# LITAF_TEMPTRESS.net
KiCad netlist of a schematic drawn in EAGLE
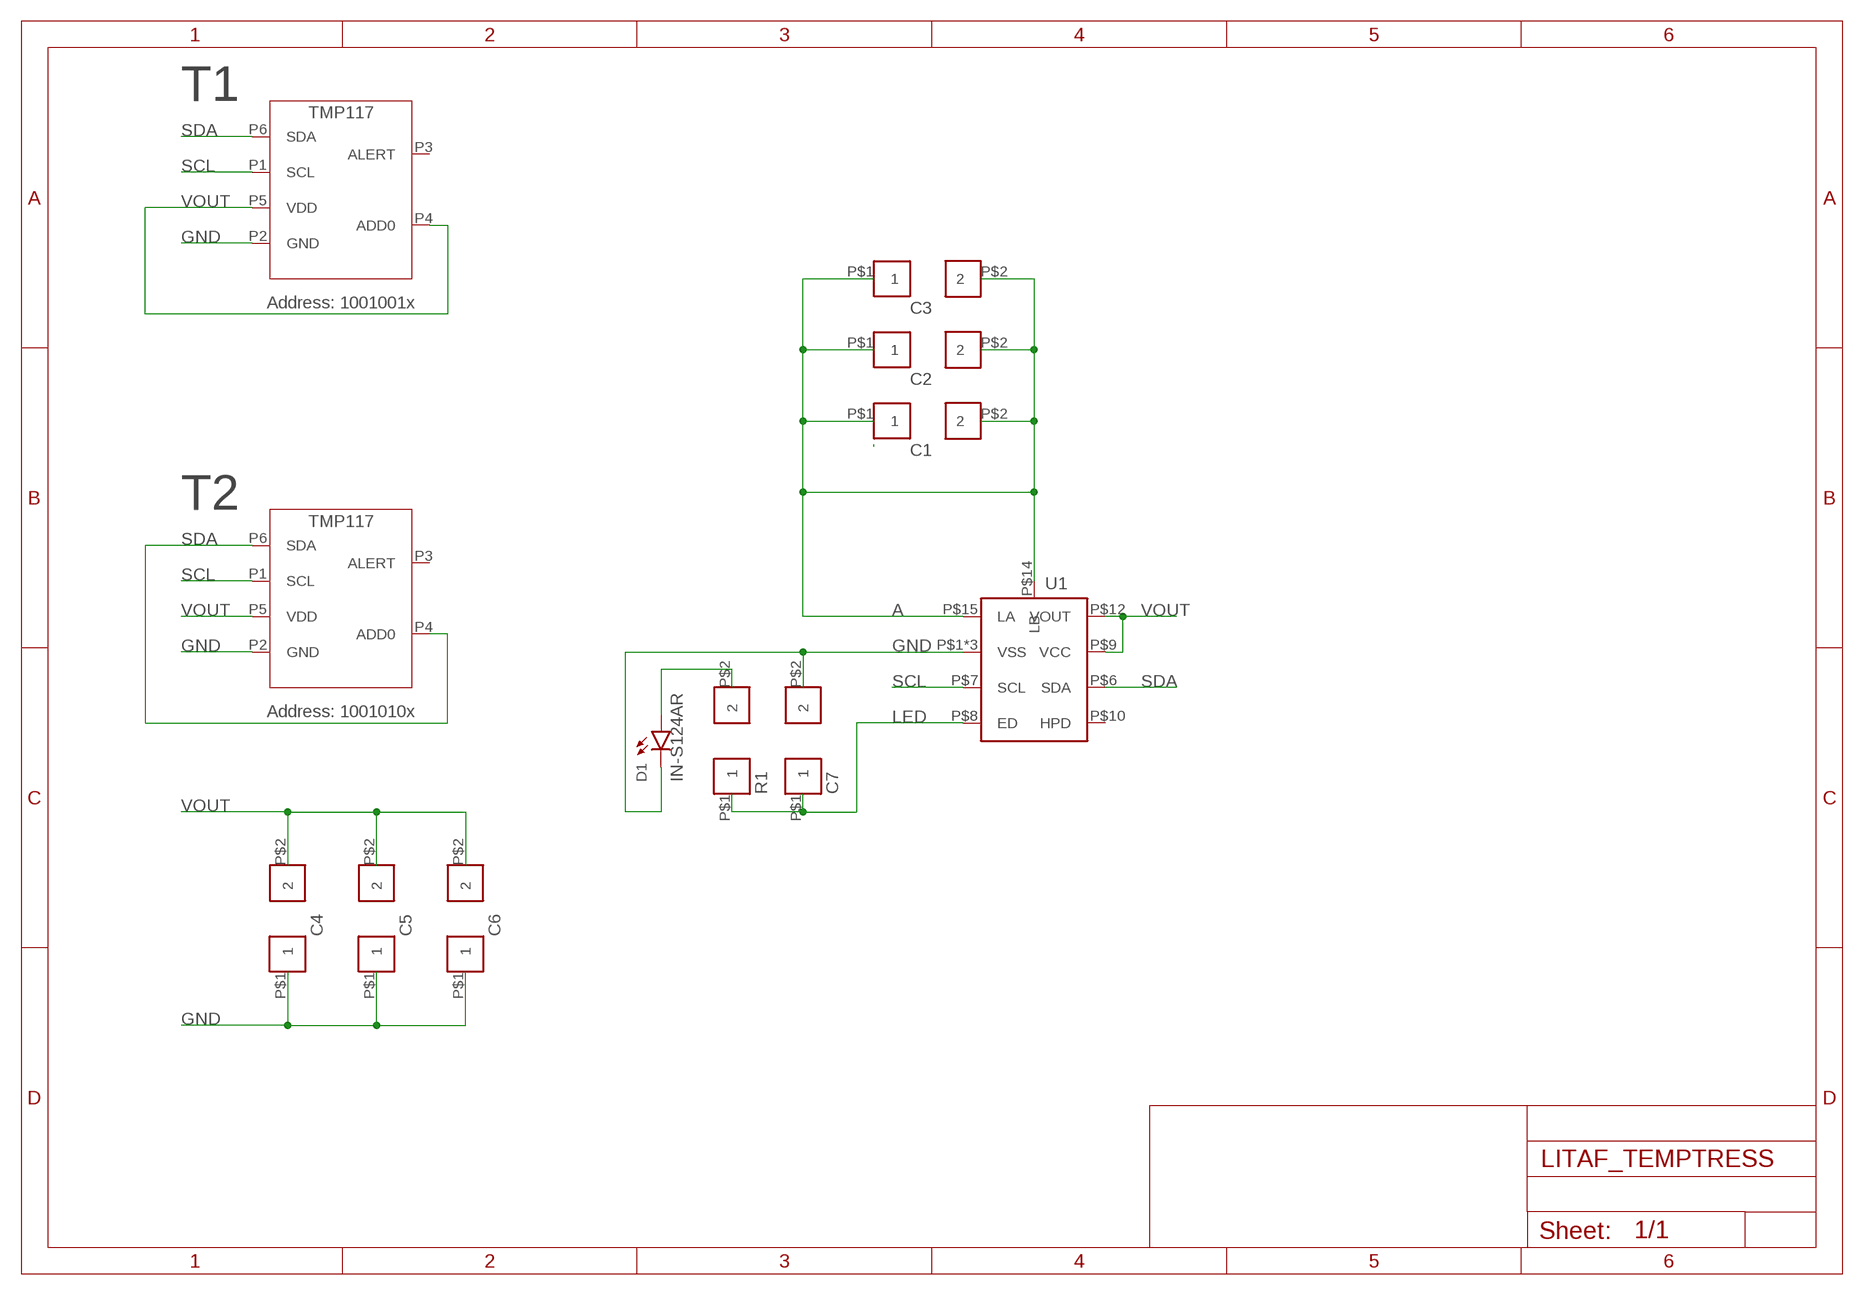
[diagram p0: schematic, sheet 1]

(export (version "E")
  (design (tool "Eeschema 10.0.6"))
  (components
    (comp (ref "C1")
      (value "0402-CAP")
      (footprint "eagle-import:0402-SMT")
      (libsource (lib "eagle-import") (part "0402-CAP"))
    )
    (comp (ref "C2")
      (value "0402-CAP")
      (footprint "eagle-import:0402-SMT")
      (libsource (lib "eagle-import") (part "0402-CAP"))
    )
    (comp (ref "C3")
      (value "0402-CAP")
      (footprint "eagle-import:0402-SMT")
      (libsource (lib "eagle-import") (part "0402-CAP"))
    )
    (comp (ref "C4")
      (value "0603-CAP")
      (footprint "eagle-import:0603-SMT[WIDE]")
      (libsource (lib "eagle-import") (part "0603-CAP"))
    )
    (comp (ref "C5")
      (value "0402-CAP")
      (footprint "eagle-import:0402-SMT")
      (libsource (lib "eagle-import") (part "0402-CAP"))
    )
    (comp (ref "C6")
      (value "0402-CAP")
      (footprint "eagle-import:0402-SMT")
      (libsource (lib "eagle-import") (part "0402-CAP"))
    )
    (comp (ref "C7")
      (value "0402-CAP")
      (footprint "eagle-import:0402-SMT")
      (libsource (lib "eagle-import") (part "0402-CAP?"))
    )
    (comp (ref "D1")
      (value "IN-S124AR")
      (footprint "eagle-import:IN-S124AR")
      (libsource (lib "eagle-import") (part "IN-S124AR"))
    )
    (comp (ref "R1")
      (value "0402-CAP")
      (footprint "eagle-import:0402-SMT")
      (libsource (lib "eagle-import") (part "0402-CAP?"))
    )
    (comp (ref "T1")
      (value "TMP117")
      (footprint "eagle-import:DRV0006B")
      (libsource (lib "eagle-import") (part "TMP117"))
    )
    (comp (ref "T2")
      (value "TMP117")
      (footprint "eagle-import:DRV0006B")
      (libsource (lib "eagle-import") (part "TMP117"))
    )
    (comp (ref "U1")
      (value "NTAG5_LINK_NTP53X2")
      (footprint "eagle-import:SOT1161-2")
      (libsource (lib "eagle-import") (part "NTAG5_LINK_NTP53X2"))
    )
  )
  (nets
    (net (code "1") (name "/A") (class "Default")
      (node (ref "C1") (pin "P$1") (pinfunction "1_P$1") (pintype "bidirectional"))
      (node (ref "C1") (pin "P$2") (pinfunction "2_P$2") (pintype "bidirectional"))
      (node (ref "C2") (pin "P$1") (pinfunction "1_P$1") (pintype "bidirectional"))
      (node (ref "C2") (pin "P$2") (pinfunction "2_P$2") (pintype "bidirectional"))
      (node (ref "C3") (pin "P$1") (pinfunction "1_P$1") (pintype "bidirectional"))
      (node (ref "C3") (pin "P$2") (pinfunction "2_P$2") (pintype "bidirectional"))
      (node (ref "U1") (pin "P$14") (pinfunction "LB_P$14") (pintype "bidirectional"))
      (node (ref "U1") (pin "P$15") (pinfunction "LA_P$15") (pintype "bidirectional"))
    )
    (net (code "2") (name "/GND") (class "Default")
      (node (ref "C4") (pin "P$1") (pinfunction "1_P$1") (pintype "bidirectional"))
      (node (ref "C5") (pin "P$1") (pinfunction "1_P$1") (pintype "bidirectional"))
      (node (ref "C6") (pin "P$1") (pinfunction "1_P$1") (pintype "bidirectional"))
      (node (ref "C7") (pin "P$2") (pinfunction "2_P$2") (pintype "bidirectional"))
      (node (ref "D1") (pin "P$2") (pinfunction "C_P$2") (pintype "passive"))
      (node (ref "T1") (pin "P2") (pinfunction "GND_P2") (pintype "bidirectional"))
      (node (ref "T2") (pin "P2") (pinfunction "GND_P2") (pintype "bidirectional"))
      (node (ref "U1") (pin "P$1") (pinfunction "VSS_P$1") (pintype "bidirectional"))
      (node (ref "U1") (pin "P$11") (pinfunction "VSS_P$11") (pintype "bidirectional"))
      (node (ref "U1") (pin "P$2") (pinfunction "VSS_P$2") (pintype "bidirectional"))
    )
    (net (code "3") (name "/LED") (class "Default")
      (node (ref "C7") (pin "P$1") (pinfunction "1_P$1") (pintype "bidirectional"))
      (node (ref "R1") (pin "P$1") (pinfunction "1_P$1") (pintype "bidirectional"))
      (node (ref "U1") (pin "P$8") (pinfunction "ED_P$8") (pintype "bidirectional"))
    )
    (net (code "4") (name "/SCL") (class "Default")
      (node (ref "T1") (pin "P1") (pinfunction "SCL_P1") (pintype "bidirectional"))
      (node (ref "T2") (pin "P1") (pinfunction "SCL_P1") (pintype "bidirectional"))
      (node (ref "U1") (pin "P$7") (pinfunction "SCL_P$7") (pintype "bidirectional"))
    )
    (net (code "5") (name "/SDA") (class "Default")
      (node (ref "T1") (pin "P6") (pinfunction "SDA_P6") (pintype "bidirectional"))
      (node (ref "T2") (pin "P4") (pinfunction "ADD0_P4") (pintype "bidirectional"))
      (node (ref "T2") (pin "P6") (pinfunction "SDA_P6") (pintype "bidirectional"))
      (node (ref "U1") (pin "P$6") (pinfunction "SDA_P$6") (pintype "bidirectional"))
    )
    (net (code "6") (name "/VOUT") (class "Default")
      (node (ref "C4") (pin "P$2") (pinfunction "2_P$2") (pintype "bidirectional"))
      (node (ref "C5") (pin "P$2") (pinfunction "2_P$2") (pintype "bidirectional"))
      (node (ref "C6") (pin "P$2") (pinfunction "2_P$2") (pintype "bidirectional"))
      (node (ref "T1") (pin "P4") (pinfunction "ADD0_P4") (pintype "bidirectional"))
      (node (ref "T1") (pin "P5") (pinfunction "VDD_P5") (pintype "bidirectional"))
      (node (ref "T2") (pin "P5") (pinfunction "VDD_P5") (pintype "bidirectional"))
      (node (ref "U1") (pin "P$12") (pinfunction "VOUT_P$12") (pintype "bidirectional"))
      (node (ref "U1") (pin "P$9") (pinfunction "VCC_P$9") (pintype "bidirectional"))
    )
    (net (code "7") (name "Net-(D1-A)") (class "Default")
      (node (ref "D1") (pin "P$1") (pinfunction "A_P$1") (pintype "passive"))
      (node (ref "R1") (pin "P$2") (pinfunction "2_P$2") (pintype "bidirectional"))
    )
    (net (code "8") (name "unconnected-(T1-ALERT-PadP3)") (class "Default")
      (node (ref "T1") (pin "P3") (pinfunction "ALERT_P3") (pintype "bidirectional"))
    )
    (net (code "9") (name "unconnected-(T2-ALERT-PadP3)") (class "Default")
      (node (ref "T2") (pin "P3") (pinfunction "ALERT_P3") (pintype "bidirectional"))
    )
    (net (code "10") (name "unconnected-(U1-HPD-PadP$10)") (class "Default")
      (node (ref "U1") (pin "P$10") (pinfunction "HPD_P$10") (pintype "bidirectional"))
    )
  )
)
